# esquematico.net
KiCad netlist of a schematic drawn in Altium Designer
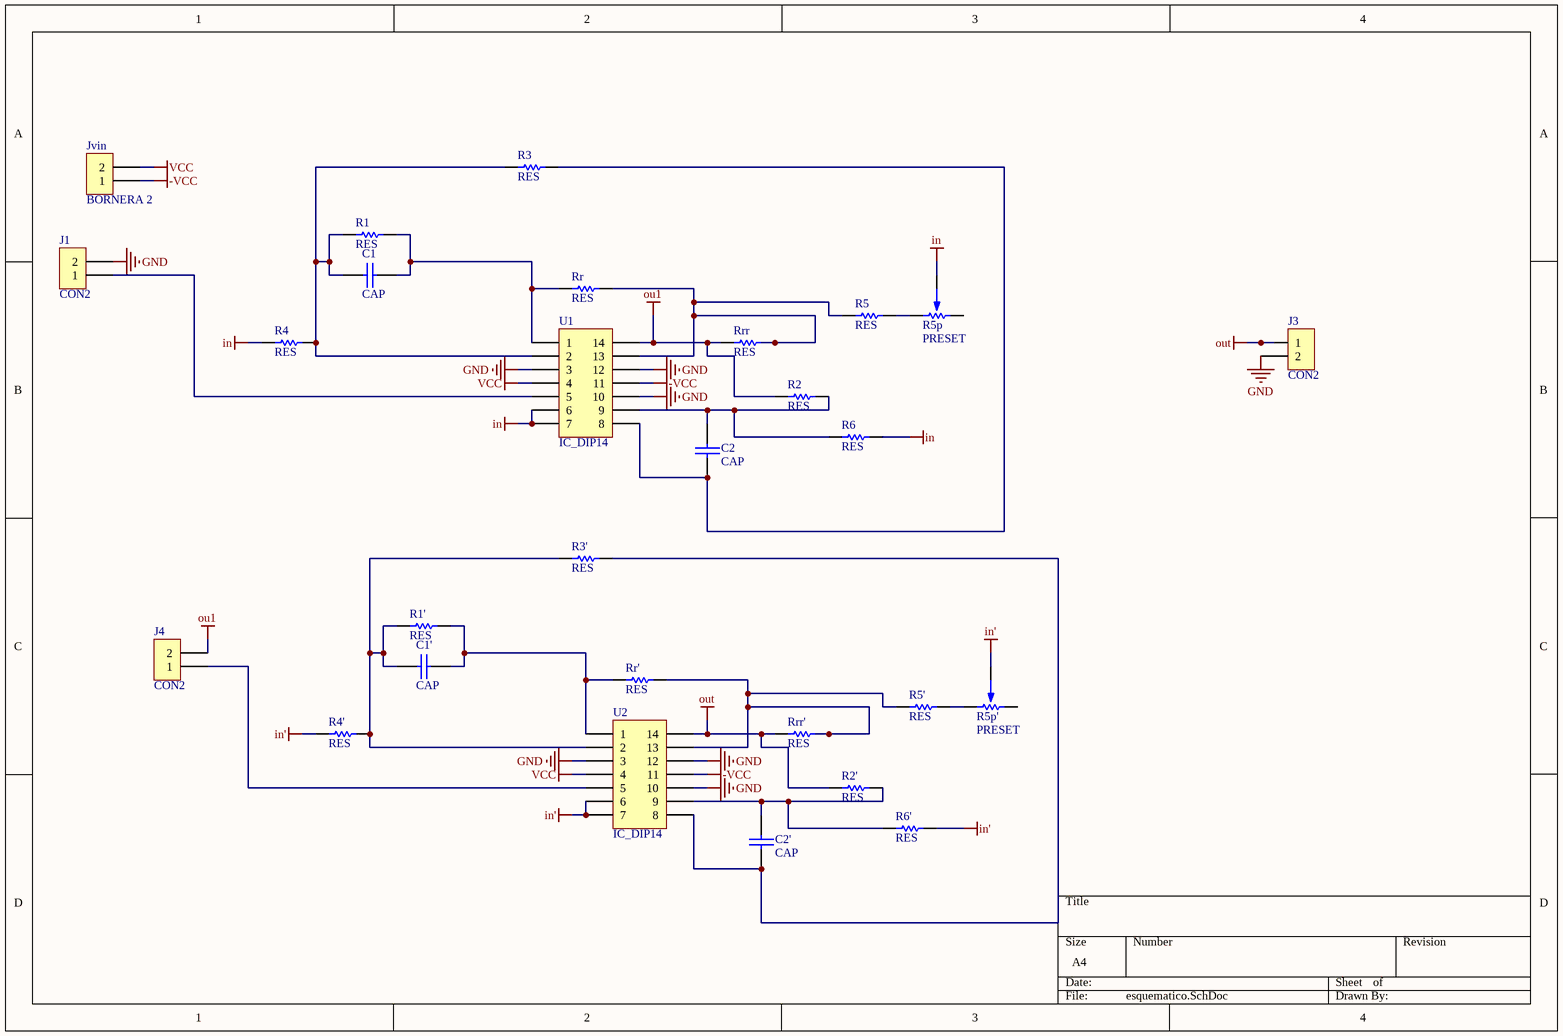
[diagram p0: esquematico.SchDoc]

(export (version "E")
  (design (tool "Eeschema 10.0.6"))
  (components
    (comp (ref "C1") (value "CAP") (footprint "CAP200") (libsource (lib "LIBEBAL") (part "CAP")))
    (comp (ref "C1'") (value "CAP") (footprint "CAP200") (libsource (lib "LIBEBAL") (part "CAP")))
    (comp (ref "C2") (value "CAP") (footprint "CAP200") (libsource (lib "LIBEBAL") (part "CAP")))
    (comp (ref "C2'") (value "CAP") (footprint "CAP200") (libsource (lib "LIBEBAL") (part "CAP")))
    (comp (ref "J1") (value "CON2") (footprint "SIP2") (libsource (lib "") (part "CON2_1")))
    (comp (ref "J3") (value "CON2") (footprint "SIP2") (libsource (lib "LIBEBAL") (part "CON2")))
    (comp (ref "J4") (value "CON2") (footprint "SIP2") (libsource (lib "") (part "CON2_1")))
    (comp (ref "Jvin")
      (value "BORNERA 2")
      (footprint "BORNERA2")
      (libsource (lib "LIBEBAL") (part "BORNERA 2"))
    )
    (comp (ref "R1") (value "RES") (footprint "RES400") (libsource (lib "LIBEBAL") (part "RES")))
    (comp (ref "R1'") (value "RES") (footprint "RES400") (libsource (lib "LIBEBAL") (part "RES")))
    (comp (ref "R2") (value "RES") (footprint "RES400") (libsource (lib "LIBEBAL") (part "RES")))
    (comp (ref "R2'") (value "RES") (footprint "RES400") (libsource (lib "LIBEBAL") (part "RES")))
    (comp (ref "R3") (value "RES") (footprint "RES400") (libsource (lib "LIBEBAL") (part "RES")))
    (comp (ref "R3'") (value "RES") (footprint "RES400") (libsource (lib "LIBEBAL") (part "RES")))
    (comp (ref "R4") (value "RES") (footprint "RES400") (libsource (lib "LIBEBAL") (part "RES")))
    (comp (ref "R4'") (value "RES") (footprint "RES400") (libsource (lib "LIBEBAL") (part "RES")))
    (comp (ref "R5") (value "RES") (footprint "RES400") (libsource (lib "LIBEBAL") (part "RES")))
    (comp (ref "R5'") (value "RES") (footprint "RES400") (libsource (lib "LIBEBAL") (part "RES")))
    (comp (ref "R5p") (value "PRESET") (footprint "PRESET H") (libsource (lib "LIBEBAL") (part "PRESET")))
    (comp (ref "R5p'") (value "PRESET") (footprint "PRESET H") (libsource (lib "LIBEBAL") (part "PRESET")))
    (comp (ref "R6") (value "RES") (footprint "RES400") (libsource (lib "LIBEBAL") (part "RES")))
    (comp (ref "R6'") (value "RES") (footprint "RES400") (libsource (lib "LIBEBAL") (part "RES")))
    (comp (ref "Rr") (value "RES") (footprint "RES400") (libsource (lib "LIBEBAL") (part "RES")))
    (comp (ref "Rr'") (value "RES") (footprint "RES400") (libsource (lib "LIBEBAL") (part "RES")))
    (comp (ref "Rrr") (value "RES") (footprint "RES400") (libsource (lib "LIBEBAL") (part "RES")))
    (comp (ref "Rrr'") (value "RES") (footprint "RES400") (libsource (lib "LIBEBAL") (part "RES")))
    (comp (ref "U1") (value "IC_DIP14") (footprint "DIP14") (libsource (lib "LIBEBAL") (part "IC_DIP14")))
    (comp (ref "U2") (value "IC_DIP14") (footprint "DIP14") (libsource (lib "LIBEBAL") (part "IC_DIP14")))
  )
  (nets
    (net (code "1") (name "-VCC") (class "Default")
      (node (ref "Jvin") (pin "1") (pinfunction "1_1") (pintype "passive"))
      (node (ref "U1") (pin "11") (pinfunction "11_11") (pintype "passive"))
      (node (ref "U2") (pin "11") (pinfunction "11_11") (pintype "passive"))
    )
    (net (code "2") (name "GND") (class "Default")
      (node (ref "J1") (pin "2") (pinfunction "2_2") (pintype "passive"))
      (node (ref "J3") (pin "2") (pinfunction "2_2") (pintype "passive"))
      (node (ref "U1") (pin "10") (pinfunction "10_10") (pintype "passive"))
      (node (ref "U1") (pin "12") (pinfunction "12_12") (pintype "passive"))
      (node (ref "U1") (pin "3") (pinfunction "3_3") (pintype "passive"))
      (node (ref "U2") (pin "10") (pinfunction "10_10") (pintype "passive"))
      (node (ref "U2") (pin "12") (pinfunction "12_12") (pintype "passive"))
      (node (ref "U2") (pin "3") (pinfunction "3_3") (pintype "passive"))
    )
    (net (code "3") (name "Net-(C1'-Pad1)") (class "Default")
      (node (ref "C1'") (pin "1") (pinfunction "1_1") (pintype "passive"))
      (node (ref "R1'") (pin "1") (pinfunction "1_1") (pintype "passive"))
      (node (ref "R3'") (pin "1") (pinfunction "1_1") (pintype "passive"))
      (node (ref "R4'") (pin "2") (pinfunction "2_2") (pintype "passive"))
      (node (ref "U2") (pin "2") (pinfunction "2_2") (pintype "passive"))
    )
    (net (code "4") (name "Net-(C1'-Pad2)") (class "Default")
      (node (ref "C1'") (pin "2") (pinfunction "2_2") (pintype "passive"))
      (node (ref "R1'") (pin "2") (pinfunction "2_2") (pintype "passive"))
      (node (ref "Rr'") (pin "1") (pinfunction "1_1") (pintype "passive"))
      (node (ref "U2") (pin "1") (pinfunction "1_1") (pintype "passive"))
    )
    (net (code "5") (name "Net-(C1-Pad1)") (class "Default")
      (node (ref "C1") (pin "1") (pinfunction "1_1") (pintype "passive"))
      (node (ref "R1") (pin "1") (pinfunction "1_1") (pintype "passive"))
      (node (ref "R3") (pin "1") (pinfunction "1_1") (pintype "passive"))
      (node (ref "R4") (pin "2") (pinfunction "2_2") (pintype "passive"))
      (node (ref "U1") (pin "2") (pinfunction "2_2") (pintype "passive"))
    )
    (net (code "6") (name "Net-(C1-Pad2)") (class "Default")
      (node (ref "C1") (pin "2") (pinfunction "2_2") (pintype "passive"))
      (node (ref "R1") (pin "2") (pinfunction "2_2") (pintype "passive"))
      (node (ref "Rr") (pin "1") (pinfunction "1_1") (pintype "passive"))
      (node (ref "U1") (pin "1") (pinfunction "1_1") (pintype "passive"))
    )
    (net (code "7") (name "Net-(C2'-Pad1)") (class "Default")
      (node (ref "C2'") (pin "1") (pinfunction "1_1") (pintype "passive"))
      (node (ref "R2'") (pin "2") (pinfunction "2_2") (pintype "passive"))
      (node (ref "R6'") (pin "1") (pinfunction "1_1") (pintype "passive"))
      (node (ref "U2") (pin "9") (pinfunction "9_9") (pintype "passive"))
    )
    (net (code "8") (name "Net-(C2'-Pad2)") (class "Default")
      (node (ref "C2'") (pin "2") (pinfunction "2_2") (pintype "passive"))
      (node (ref "R3'") (pin "2") (pinfunction "2_2") (pintype "passive"))
      (node (ref "U2") (pin "8") (pinfunction "8_8") (pintype "passive"))
    )
    (net (code "9") (name "Net-(C2-Pad1)") (class "Default")
      (node (ref "C2") (pin "1") (pinfunction "1_1") (pintype "passive"))
      (node (ref "R2") (pin "2") (pinfunction "2_2") (pintype "passive"))
      (node (ref "R6") (pin "1") (pinfunction "1_1") (pintype "passive"))
      (node (ref "U1") (pin "9") (pinfunction "9_9") (pintype "passive"))
    )
    (net (code "10") (name "Net-(C2-Pad2)") (class "Default")
      (node (ref "C2") (pin "2") (pinfunction "2_2") (pintype "passive"))
      (node (ref "R3") (pin "2") (pinfunction "2_2") (pintype "passive"))
      (node (ref "U1") (pin "8") (pinfunction "8_8") (pintype "passive"))
    )
    (net (code "11") (name "Net-(J1-Pad1)") (class "Default")
      (node (ref "J1") (pin "1") (pinfunction "1_1") (pintype "passive"))
      (node (ref "U1") (pin "5") (pinfunction "5_5") (pintype "passive"))
    )
    (net (code "12") (name "Net-(J4-Pad1)") (class "Default")
      (node (ref "J4") (pin "1") (pinfunction "1_1") (pintype "passive"))
      (node (ref "U2") (pin "5") (pinfunction "5_5") (pintype "passive"))
    )
    (net (code "13") (name "Net-(R5'-Pad1)") (class "Default")
      (node (ref "R5'") (pin "1") (pinfunction "1_1") (pintype "passive"))
      (node (ref "Rr'") (pin "2") (pinfunction "2_2") (pintype "passive"))
      (node (ref "Rrr'") (pin "2") (pinfunction "2_2") (pintype "passive"))
      (node (ref "U2") (pin "13") (pinfunction "13_13") (pintype "passive"))
    )
    (net (code "14") (name "Net-(R5'-Pad2)") (class "Default")
      (node (ref "R5'") (pin "2") (pinfunction "2_2") (pintype "passive"))
      (node (ref "R5p'") (pin "1") (pinfunction "1_1") (pintype "passive"))
    )
    (net (code "15") (name "Net-(R5-Pad1)") (class "Default")
      (node (ref "R5") (pin "1") (pinfunction "1_1") (pintype "passive"))
      (node (ref "Rr") (pin "2") (pinfunction "2_2") (pintype "passive"))
      (node (ref "Rrr") (pin "2") (pinfunction "2_2") (pintype "passive"))
      (node (ref "U1") (pin "13") (pinfunction "13_13") (pintype "passive"))
    )
    (net (code "16") (name "Net-(R5-Pad2)") (class "Default")
      (node (ref "R5") (pin "2") (pinfunction "2_2") (pintype "passive"))
      (node (ref "R5p") (pin "1") (pinfunction "1_1") (pintype "passive"))
    )
    (net (code "17") (name "VCC") (class "Default")
      (node (ref "Jvin") (pin "2") (pinfunction "2_2") (pintype "passive"))
      (node (ref "U1") (pin "4") (pinfunction "4_4") (pintype "passive"))
      (node (ref "U2") (pin "4") (pinfunction "4_4") (pintype "passive"))
    )
    (net (code "18") (name "in") (class "Default")
      (node (ref "R4") (pin "1") (pinfunction "1_1") (pintype "passive"))
      (node (ref "R5p") (pin "2") (pinfunction "2_2") (pintype "passive"))
      (node (ref "R6") (pin "2") (pinfunction "2_2") (pintype "passive"))
      (node (ref "U1") (pin "6") (pinfunction "6_6") (pintype "passive"))
      (node (ref "U1") (pin "7") (pinfunction "7_7") (pintype "passive"))
    )
    (net (code "19") (name "in'") (class "Default")
      (node (ref "R4'") (pin "1") (pinfunction "1_1") (pintype "passive"))
      (node (ref "R5p'") (pin "2") (pinfunction "2_2") (pintype "passive"))
      (node (ref "R6'") (pin "2") (pinfunction "2_2") (pintype "passive"))
      (node (ref "U2") (pin "6") (pinfunction "6_6") (pintype "passive"))
      (node (ref "U2") (pin "7") (pinfunction "7_7") (pintype "passive"))
    )
    (net (code "20") (name "ou1") (class "Default")
      (node (ref "J4") (pin "2") (pinfunction "2_2") (pintype "passive"))
      (node (ref "R2") (pin "1") (pinfunction "1_1") (pintype "passive"))
      (node (ref "Rrr") (pin "1") (pinfunction "1_1") (pintype "passive"))
      (node (ref "U1") (pin "14") (pinfunction "14_14") (pintype "passive"))
    )
    (net (code "21") (name "out") (class "Default")
      (node (ref "J3") (pin "1") (pinfunction "1_1") (pintype "passive"))
      (node (ref "R2'") (pin "1") (pinfunction "1_1") (pintype "passive"))
      (node (ref "Rrr'") (pin "1") (pinfunction "1_1") (pintype "passive"))
      (node (ref "U2") (pin "14") (pinfunction "14_14") (pintype "passive"))
    )
    (net (code "22") (name "unconnected-(R5p'-Pad3)") (class "Default")
      (node (ref "R5p'") (pin "3") (pinfunction "3_3") (pintype "passive"))
    )
    (net (code "23") (name "unconnected-(R5p-Pad3)") (class "Default")
      (node (ref "R5p") (pin "3") (pinfunction "3_3") (pintype "passive"))
    )
  )
)
